# 08_Connectors_STM32_A.net
KiCad netlist of a schematic drawn in Altium Designer
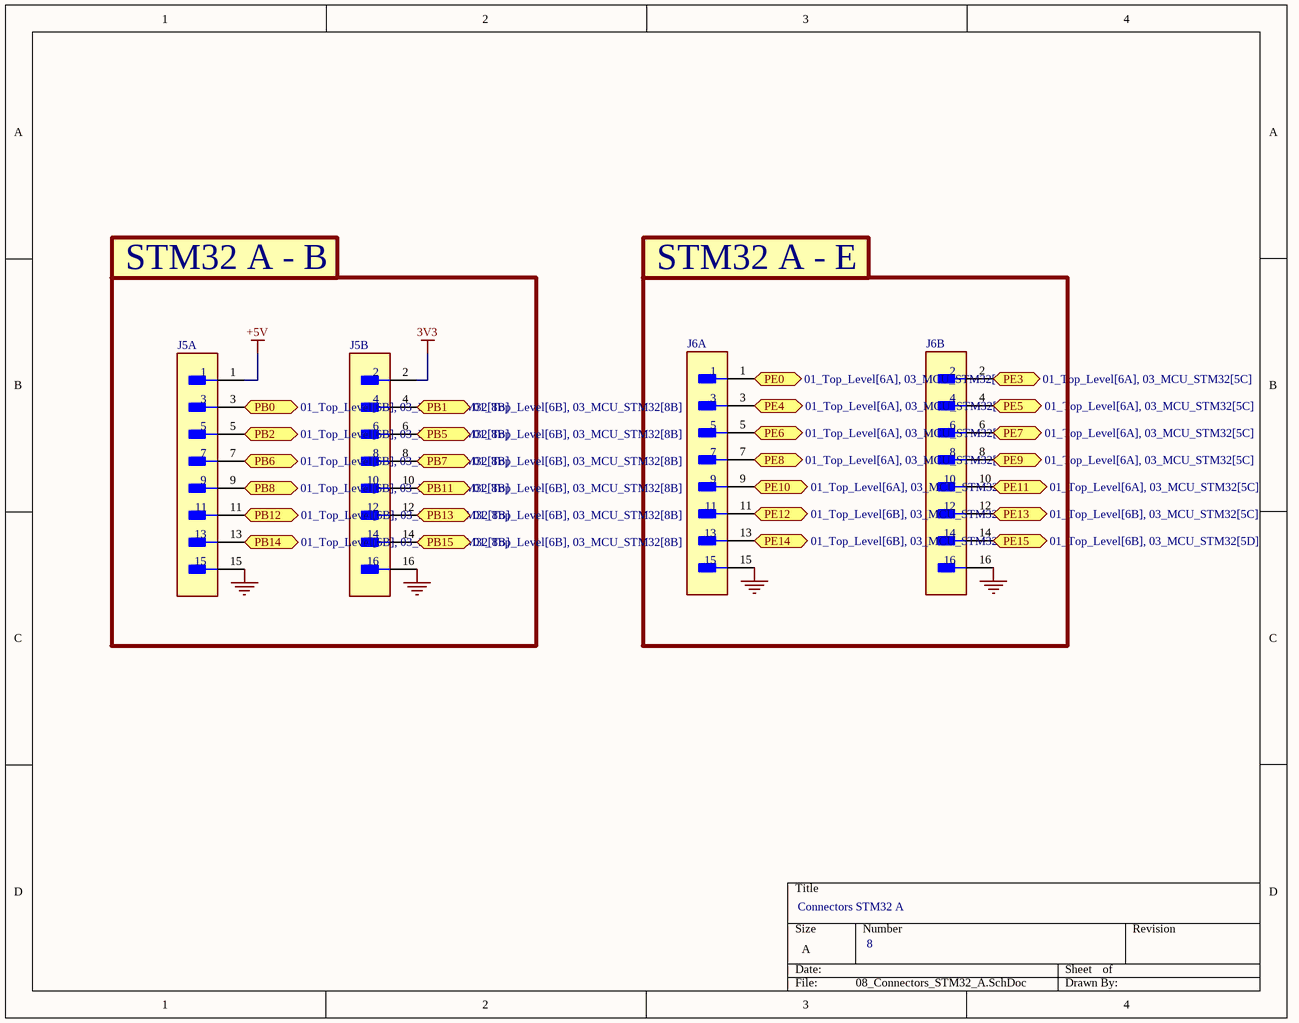
[diagram p0: 08_Connectors_STM32_A.SchDoc]

(export (version "E")
  (design (tool "Eeschema 10.0.6"))
  (components
    (comp (ref "J5")
      (value "GRPB082MWCN-RC")
      (footprint "FP-GRPB082MWCN-RC-MFG")
      (description "CONN HEADER R/A 16POS 1.27MM")
      (libsource (lib "Altium Content Vault") (part "ecabc7128bd599dbeade09ffe984aba"))
    )
    (comp (ref "J6")
      (value "GRPB082MWCN-RC")
      (footprint "FP-GRPB082MWCN-RC-MFG")
      (description "CONN HEADER R/A 16POS 1.27MM")
      (libsource (lib "Altium Content Vault") (part "ecabc7128bd599dbeade09ffe984aba"))
    )
  )
  (nets
    (net (code "1") (name "+5V") (class "Default")
      (node (ref "J5") (pin "1") (pinfunction "1_1") (pintype "passive"))
    )
    (net (code "2") (name "/PB0") (class "Default")
      (node (ref "J5") (pin "3") (pinfunction "3_3") (pintype "passive"))
    )
    (net (code "3") (name "/PB1") (class "Default")
      (node (ref "J5") (pin "4") (pinfunction "4_4") (pintype "passive"))
    )
    (net (code "4") (name "/PB2") (class "Default")
      (node (ref "J5") (pin "5") (pinfunction "5_5") (pintype "passive"))
    )
    (net (code "5") (name "/PB5") (class "Default")
      (node (ref "J5") (pin "6") (pinfunction "6_6") (pintype "passive"))
    )
    (net (code "6") (name "/PB6") (class "Default")
      (node (ref "J5") (pin "7") (pinfunction "7_7") (pintype "passive"))
    )
    (net (code "7") (name "/PB7") (class "Default")
      (node (ref "J5") (pin "8") (pinfunction "8_8") (pintype "passive"))
    )
    (net (code "8") (name "/PB8") (class "Default")
      (node (ref "J5") (pin "9") (pinfunction "9_9") (pintype "passive"))
    )
    (net (code "9") (name "/PB11") (class "Default")
      (node (ref "J5") (pin "10") (pinfunction "10_10") (pintype "passive"))
    )
    (net (code "10") (name "/PB12") (class "Default")
      (node (ref "J5") (pin "11") (pinfunction "11_11") (pintype "passive"))
    )
    (net (code "11") (name "/PB13") (class "Default")
      (node (ref "J5") (pin "12") (pinfunction "12_12") (pintype "passive"))
    )
    (net (code "12") (name "/PB14") (class "Default")
      (node (ref "J5") (pin "13") (pinfunction "13_13") (pintype "passive"))
    )
    (net (code "13") (name "/PB15") (class "Default")
      (node (ref "J5") (pin "14") (pinfunction "14_14") (pintype "passive"))
    )
    (net (code "14") (name "/PE0") (class "Default")
      (node (ref "J6") (pin "1") (pinfunction "1_1") (pintype "passive"))
    )
    (net (code "15") (name "/PE3") (class "Default")
      (node (ref "J6") (pin "2") (pinfunction "2_2") (pintype "passive"))
    )
    (net (code "16") (name "/PE4") (class "Default")
      (node (ref "J6") (pin "3") (pinfunction "3_3") (pintype "passive"))
    )
    (net (code "17") (name "/PE5") (class "Default")
      (node (ref "J6") (pin "4") (pinfunction "4_4") (pintype "passive"))
    )
    (net (code "18") (name "/PE6") (class "Default")
      (node (ref "J6") (pin "5") (pinfunction "5_5") (pintype "passive"))
    )
    (net (code "19") (name "/PE7") (class "Default")
      (node (ref "J6") (pin "6") (pinfunction "6_6") (pintype "passive"))
    )
    (net (code "20") (name "/PE8") (class "Default")
      (node (ref "J6") (pin "7") (pinfunction "7_7") (pintype "passive"))
    )
    (net (code "21") (name "/PE9") (class "Default")
      (node (ref "J6") (pin "8") (pinfunction "8_8") (pintype "passive"))
    )
    (net (code "22") (name "/PE10") (class "Default")
      (node (ref "J6") (pin "9") (pinfunction "9_9") (pintype "passive"))
    )
    (net (code "23") (name "/PE11") (class "Default")
      (node (ref "J6") (pin "10") (pinfunction "10_10") (pintype "passive"))
    )
    (net (code "24") (name "/PE12") (class "Default")
      (node (ref "J6") (pin "11") (pinfunction "11_11") (pintype "passive"))
    )
    (net (code "25") (name "/PE13") (class "Default")
      (node (ref "J6") (pin "12") (pinfunction "12_12") (pintype "passive"))
    )
    (net (code "26") (name "/PE14") (class "Default")
      (node (ref "J6") (pin "13") (pinfunction "13_13") (pintype "passive"))
    )
    (net (code "27") (name "/PE15") (class "Default")
      (node (ref "J6") (pin "14") (pinfunction "14_14") (pintype "passive"))
    )
    (net (code "28") (name "3V3") (class "Default")
      (node (ref "J5") (pin "2") (pinfunction "2_2") (pintype "passive"))
    )
    (net (code "29") (name "GND") (class "Default")
      (node (ref "J5") (pin "15") (pinfunction "15_15") (pintype "passive"))
      (node (ref "J5") (pin "16") (pinfunction "16_16") (pintype "passive"))
      (node (ref "J6") (pin "15") (pinfunction "15_15") (pintype "passive"))
      (node (ref "J6") (pin "16") (pinfunction "16_16") (pintype "passive"))
    )
  )
)
